# 12V_TO_5V_DC.net
KiCad netlist of a schematic drawn in Altium Designer
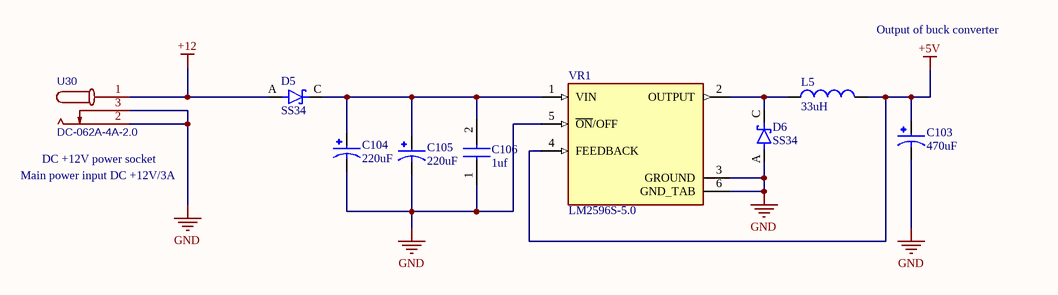
[diagram p0: 12V_TO_5V_DC.SchDoc]

(export (version "E")
  (design (tool "Eeschema 10.0.6"))
  (components
    (comp (ref "C103")
      (value "470uF")
      (footprint "Plugin,6.3x8mm")
      (description "6.3V 470uF ±20% Plugin,6.3x8mm Solid Capacitors ROHS")
      (fields (field (name "MPN") "EEE-HC1H101P") (field (name "MANUFACTURER") "Panasonic"))
      (libsource (lib "RCL") (part "SPTOJM471E08OR"))
    )
    (comp (ref "C104")
      (value "220uF")
      (footprint "Plugin,6.3x8mm")
      (description "16V 220uF ±20% 20mΩ@100kHz 2.7A@100kHz Plugin,6.3x8mm Solid Capacitors ROHS")
      (fields (field (name "MPN") "EEE-HC1H101P") (field (name "MANUFACTURER") "Panasonic"))
      (libsource (lib "RCL") (part "SPZ1CM221E08O00RAXXX"))
    )
    (comp (ref "C105")
      (value "220uF")
      (footprint "Plugin,6.3x8mm")
      (description "16V 220uF ±20% 20mΩ@100kHz 2.7A@100kHz Plugin,6.3x8mm Solid Capacitors ROHS")
      (fields (field (name "MPN") "EEE-HC1H101P") (field (name "MANUFACTURER") "Panasonic"))
      (libsource (lib "RCL") (part "SPZ1CM221E08O00RAXXX"))
    )
    (comp (ref "C106")
      (value "1uf")
      (footprint "C0805")
      (description "50V 1uF X7R ±10% 0805 Multilayer Ceramic Capacitors MLCC - SMD/SMT ROHS")
      (fields (field (name "MANUFACTURER") "KEMET") (field (name "MPN") "CC0603JRNPO9BN180"))
      (libsource (lib "RCL") (part "CL21B105KBFNNNE"))
    )
    (comp (ref "D5")
      (value "SS34")
      (footprint "SMA")
      (description "Diode Schottky 40V 3A 2-Pin SMC T/R")
      (libsource (lib "RCL_SCH_LIB") (part "SS34"))
    )
    (comp (ref "D6")
      (value "SS34")
      (footprint "SMA")
      (description "Diode Schottky 40V 3A 2-Pin SMC T/R")
      (libsource (lib "RCL") (part "SS34"))
    )
    (comp (ref "L5")
      (value "33uH")
      (footprint "Inductor")
      (description "3A 33uH ±20% 64.8mΩ SMD Power Inductors ROHS")
      (fields (field (name "MPN") "AIML-0805HC-100M-T") (field (name "MANUFACTURER") "Abracon"))
      (libsource (lib "RCL") (part "SLH1207S330MTT"))
    )
    (comp (ref "U30")
      (value "DC-062A-4A-2.0")
      (footprint "Plugin")
      (libsource (lib "connector_button") (part "DC-062A-4A-2.0"))
    )
    (comp (ref "VR1")
      (value "LM2596S-5.0")
      (footprint "TO-263-5")
      (description "Step-down type Fixed 40V~40V 5V 3A TO-263-5 DC-DC Converters ROHS")
      (libsource (lib "IC") (part "LM2596S-5.0"))
    )
  )
  (nets
    (net (code "1") (name "+5V") (class "Default")
      (node (ref "C103") (pin "1") (pinfunction "1_1") (pintype "passive"))
      (node (ref "L5") (pin "2") (pinfunction "2_2") (pintype "passive"))
      (node (ref "VR1") (pin "4") (pinfunction "FEEDBACK_4") (pintype "input"))
    )
    (net (code "2") (name "+12") (class "Default")
      (node (ref "D5") (pin "A") (pinfunction "A_A") (pintype "passive"))
      (node (ref "U30") (pin "1") (pinfunction "1_1") (pintype "passive"))
    )
    (net (code "3") (name "GND") (class "Default")
      (node (ref "C103") (pin "2") (pinfunction "2_2") (pintype "passive"))
      (node (ref "C104") (pin "2") (pinfunction "2_2") (pintype "passive"))
      (node (ref "C105") (pin "2") (pinfunction "2_2") (pintype "passive"))
      (node (ref "C106") (pin "1") (pinfunction "C1_1") (pintype "passive"))
      (node (ref "D6") (pin "A") (pinfunction "A_A") (pintype "passive"))
      (node (ref "U30") (pin "2") (pinfunction "2_2") (pintype "passive"))
      (node (ref "U30") (pin "3") (pinfunction "3_3") (pintype "passive"))
      (node (ref "VR1") (pin "3") (pinfunction "GROUND_3") (pintype "power_in"))
      (node (ref "VR1") (pin "5") (pinfunction "~{ON}/OFF_5") (pintype "input"))
      (node (ref "VR1") (pin "6") (pinfunction "GND_TAB_6") (pintype "power_in"))
    )
    (net (code "4") (name "Net-(C106-C2)") (class "Default")
      (node (ref "C104") (pin "1") (pinfunction "1_1") (pintype "passive"))
      (node (ref "C105") (pin "1") (pinfunction "1_1") (pintype "passive"))
      (node (ref "C106") (pin "2") (pinfunction "C2_2") (pintype "passive"))
      (node (ref "D5") (pin "C") (pinfunction "K_C") (pintype "passive"))
      (node (ref "VR1") (pin "1") (pinfunction "VIN_1") (pintype "input"))
    )
    (net (code "5") (name "Net-(D6-K)") (class "Default")
      (node (ref "D6") (pin "C") (pinfunction "K_C") (pintype "passive"))
      (node (ref "L5") (pin "1") (pinfunction "1_1") (pintype "passive"))
      (node (ref "VR1") (pin "2") (pinfunction "OUTPUT_2") (pintype "output"))
    )
  )
)
